# DemoCatV2.net
KiCad netlist of a schematic drawn in Altium Designer
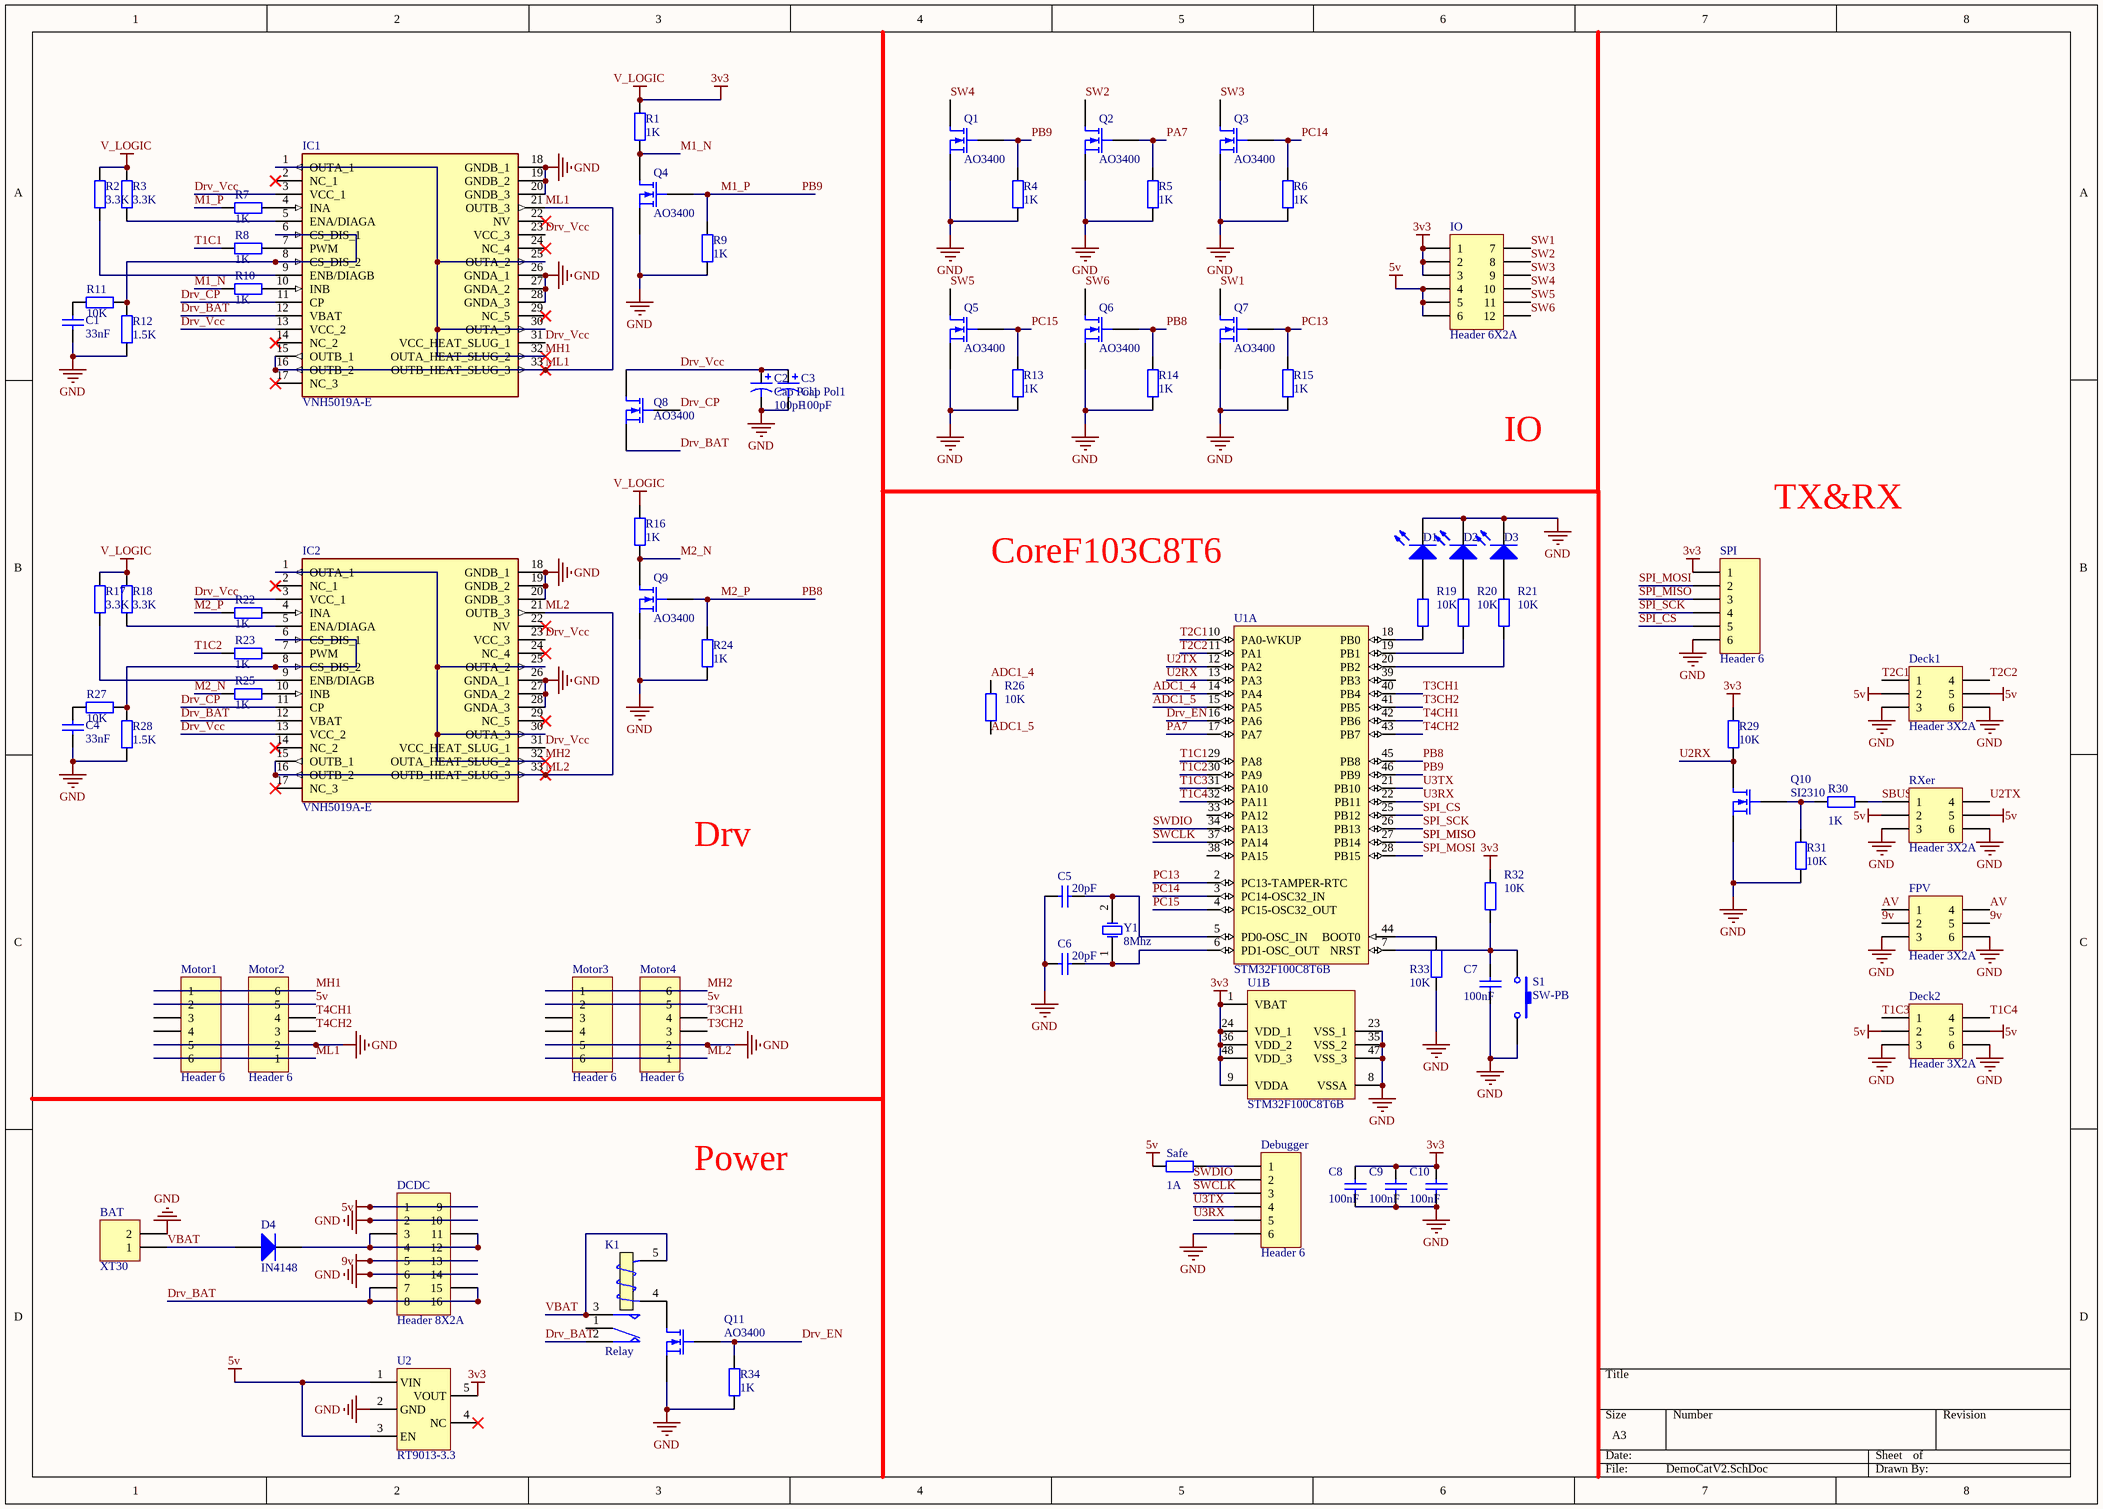
[diagram p0: DemoCatV2.SchDoc]

(export (version "E")
  (design (tool "Eeschema 10.0.6"))
  (components
    (comp (ref "BAT")
      (value "XT30")
      (footprint "XT30-IN-W")
      (description "Header, 2-Pin")
      (fields (field (name "PUBLISHER") "Altium Limited"))
      (libsource (lib "Miscellaneous Connectors") (part "Header 2"))
    )
    (comp (ref "C1")
      (value "33nF")
      (footprint "0603C")
      (description "Capacitor")
      (fields (field (name "Comment") "Cap") (field (name "PUBLISHER") "Altium Limited"))
      (libsource (lib "Miscellaneous Devices") (part "Cap"))
    )
    (comp (ref "C2")
      (value "Cap Pol1")
      (footprint "6.3*7.7-c")
      (description "Polarized Capacitor (Radial)")
      (fields (field (name "ALTIUM_VALUE") "100pF") (field (name "PUBLISHER") "Altium Limited"))
      (libsource (lib "Miscellaneous Devices") (part "Cap Pol1"))
    )
    (comp (ref "C3")
      (value "Cap Pol1")
      (footprint "6.3*7.7-c")
      (description "Polarized Capacitor (Radial)")
      (fields (field (name "ALTIUM_VALUE") "100pF") (field (name "PUBLISHER") "Altium Limited"))
      (libsource (lib "Miscellaneous Devices") (part "Cap Pol1"))
    )
    (comp (ref "C4")
      (value "33nF")
      (footprint "0603C")
      (description "Capacitor")
      (fields (field (name "Comment") "Cap") (field (name "PUBLISHER") "Altium Limited"))
      (libsource (lib "Miscellaneous Devices") (part "Cap"))
    )
    (comp (ref "C5")
      (value "20pF")
      (footprint "0603C")
      (description "Capacitor")
      (fields (field (name "Comment") "Cap") (field (name "PUBLISHER") "Altium Limited"))
      (libsource (lib "Miscellaneous Devices") (part "Cap"))
    )
    (comp (ref "C6")
      (value "20pF")
      (footprint "0603C")
      (description "Capacitor")
      (fields (field (name "Comment") "Cap") (field (name "PUBLISHER") "Altium Limited"))
      (libsource (lib "Miscellaneous Devices") (part "Cap"))
    )
    (comp (ref "C7")
      (value "100nF")
      (footprint "0603C")
      (description "Capacitor")
      (fields (field (name "Comment") "Cap") (field (name "PUBLISHER") "Altium Limited"))
      (libsource (lib "Miscellaneous Devices") (part "Cap"))
    )
    (comp (ref "C8")
      (value "100nF")
      (footprint "0603C")
      (description "Capacitor")
      (fields (field (name "Comment") "Cap") (field (name "PUBLISHER") "Altium Limited"))
      (libsource (lib "Miscellaneous Devices") (part "Cap"))
    )
    (comp (ref "C9")
      (value "100nF")
      (footprint "0603C")
      (description "Capacitor")
      (fields (field (name "Comment") "Cap") (field (name "PUBLISHER") "Altium Limited"))
      (libsource (lib "Miscellaneous Devices") (part "Cap"))
    )
    (comp (ref "C10")
      (value "100nF")
      (footprint "0603C")
      (description "Capacitor")
      (fields (field (name "Comment") "Cap") (field (name "PUBLISHER") "Altium Limited"))
      (libsource (lib "Miscellaneous Devices") (part "Cap"))
    )
    (comp (ref "D1")
      (value "LED0")
      (footprint "0603LED - Red")
      (description "Typical INFRARED GaAs LED")
      (fields (field (name "PUBLISHER") "Altium Limited"))
      (libsource (lib "Miscellaneous Devices") (part "LED0"))
    )
    (comp (ref "D2")
      (value "LED0")
      (footprint "0603LED - Green")
      (description "Typical INFRARED GaAs LED")
      (fields (field (name "PUBLISHER") "Altium Limited"))
      (libsource (lib "Miscellaneous Devices") (part "LED0"))
    )
    (comp (ref "D3")
      (value "LED0")
      (footprint "0603LED - Blue")
      (description "Typical INFRARED GaAs LED")
      (fields (field (name "PUBLISHER") "Altium Limited"))
      (libsource (lib "Miscellaneous Devices") (part "LED0"))
    )
    (comp (ref "D4")
      (value "IN4148")
      (footprint "DO-214AA(SMB)")
      (description "Default Diode")
      (fields (field (name "PUBLISHER") "Altium Limited"))
      (libsource (lib "Miscellaneous Devices") (part "Diode"))
    )
    (comp (ref "DCDC")
      (value "Header 8X2A")
      (footprint "HDR_EDGE_2x8")
      (description "Header, 8-Pin, Dual row")
      (fields (field (name "PUBLISHER") "Altium Limited"))
      (libsource (lib "Miscellaneous Connectors") (part "Header 8X2A"))
    )
    (comp (ref "Debugger")
      (value "Header 6")
      (footprint "GX1.25_T_6P")
      (description "Header, 6-Pin")
      (fields (field (name "PUBLISHER") "Altium Limited"))
      (libsource (lib "") (part "Header 6_1"))
    )
    (comp (ref "Deck1")
      (value "Header 3X2A")
      (footprint "HDR_EDGE_2x3")
      (description "Header, 3-Pin, Dual row")
      (fields (field (name "PUBLISHER") "Altium Limited"))
      (libsource (lib "Miscellaneous Connectors") (part "Header 3X2A"))
    )
    (comp (ref "Deck2")
      (value "Header 3X2A")
      (footprint "HDR_EDGE_2x3")
      (description "Header, 3-Pin, Dual row")
      (fields (field (name "PUBLISHER") "Altium Limited"))
      (libsource (lib "Miscellaneous Connectors") (part "Header 3X2A"))
    )
    (comp (ref "FPV")
      (value "Header 3X2A")
      (footprint "HDR_EDGE_2x3")
      (description "Header, 3-Pin, Dual row")
      (fields (field (name "PUBLISHER") "Altium Limited"))
      (libsource (lib "Miscellaneous Connectors") (part "Header 3X2A"))
    )
    (comp (ref "IC1")
      (value "VNH5019A-E")
      (footprint "VNH5019A-E_1")
      (description "Integrated Circuit")
      (fields (field (name "MOUSER PART NUMBER") "511-VNH5019A-E") (field (name "RS PART NUMBER") "8805550P"))
      (libsource (lib "*") (part "VNH5019A-E"))
    )
    (comp (ref "IC2")
      (value "VNH5019A-E")
      (footprint "VNH5019A-E_1")
      (description "Integrated Circuit")
      (fields (field (name "MOUSER PART NUMBER") "511-VNH5019A-E") (field (name "RS PART NUMBER") "8805550P"))
      (libsource (lib "*") (part "VNH5019A-E"))
    )
    (comp (ref "IO")
      (value "Header 6X2A")
      (footprint "HDR_EDGE_2x6")
      (description "Header, 6-Pin, Dual row")
      (fields (field (name "PUBLISHER") "Altium Limited"))
      (libsource (lib "Miscellaneous Connectors") (part "Header 6X2A"))
    )
    (comp (ref "K1")
      (value "Relay")
      (footprint "RY-HF46-HS1")
      (description "SPDT Relay")
      (fields (field (name "PUBLISHER") "Altium Limited"))
      (libsource (lib "Relay") (part "Relay"))
    )
    (comp (ref "Motor1")
      (value "Header 6")
      (footprint "PH-PS-2.0-6")
      (description "Header, 6-Pin")
      (fields (field (name "PUBLISHER") "Altium Limited"))
      (libsource (lib "") (part "Header 6_1"))
    )
    (comp (ref "Motor2")
      (value "Header 6")
      (footprint "PH-PS-2.0-6")
      (description "Header, 6-Pin")
      (fields (field (name "PUBLISHER") "Altium Limited"))
      (libsource (lib "Miscellaneous Connectors") (part "Header 6"))
    )
    (comp (ref "Motor3")
      (value "Header 6")
      (footprint "PH-PS-2.0-6")
      (description "Header, 6-Pin")
      (fields (field (name "PUBLISHER") "Altium Limited"))
      (libsource (lib "") (part "Header 6_1"))
    )
    (comp (ref "Motor4")
      (value "Header 6")
      (footprint "PH-PS-2.0-6")
      (description "Header, 6-Pin")
      (fields (field (name "PUBLISHER") "Altium Limited"))
      (libsource (lib "Miscellaneous Connectors") (part "Header 6"))
    )
    (comp (ref "Q1")
      (value "AO3400")
      (footprint "SOT-23-MOS")
      (description "N-Channel MOSFET")
      (fields (field (name "PUBLISHER") "Altium Limited"))
      (libsource (lib "Miscellaneous Devices") (part "MOSFET-N"))
    )
    (comp (ref "Q2")
      (value "AO3400")
      (footprint "SOT-23-MOS")
      (description "N-Channel MOSFET")
      (fields (field (name "PUBLISHER") "Altium Limited"))
      (libsource (lib "Miscellaneous Devices") (part "MOSFET-N"))
    )
    (comp (ref "Q3")
      (value "AO3400")
      (footprint "SOT-23-MOS")
      (description "N-Channel MOSFET")
      (fields (field (name "PUBLISHER") "Altium Limited"))
      (libsource (lib "Miscellaneous Devices") (part "MOSFET-N"))
    )
    (comp (ref "Q4")
      (value "AO3400")
      (footprint "SOT-23-MOS")
      (description "N-Channel MOSFET")
      (fields (field (name "PUBLISHER") "Altium Limited"))
      (libsource (lib "Miscellaneous Devices") (part "MOSFET-N"))
    )
    (comp (ref "Q5")
      (value "AO3400")
      (footprint "SOT-23-MOS")
      (description "N-Channel MOSFET")
      (fields (field (name "PUBLISHER") "Altium Limited"))
      (libsource (lib "Miscellaneous Devices") (part "MOSFET-N"))
    )
    (comp (ref "Q6")
      (value "AO3400")
      (footprint "SOT-23-MOS")
      (description "N-Channel MOSFET")
      (fields (field (name "PUBLISHER") "Altium Limited"))
      (libsource (lib "Miscellaneous Devices") (part "MOSFET-N"))
    )
    (comp (ref "Q7")
      (value "AO3400")
      (footprint "SOT-23-MOS")
      (description "N-Channel MOSFET")
      (fields (field (name "PUBLISHER") "Altium Limited"))
      (libsource (lib "Miscellaneous Devices") (part "MOSFET-N"))
    )
    (comp (ref "Q8")
      (value "AO3400")
      (footprint "TO-252-3")
      (description "N-Channel MOSFET")
      (fields (field (name "PUBLISHER") "Altium Limited"))
      (libsource (lib "Miscellaneous Devices") (part "MOSFET-N"))
    )
    (comp (ref "Q9")
      (value "AO3400")
      (footprint "SOT-23-MOS")
      (description "N-Channel MOSFET")
      (fields (field (name "PUBLISHER") "Altium Limited"))
      (libsource (lib "Miscellaneous Devices") (part "MOSFET-N"))
    )
    (comp (ref "Q10")
      (value "SI2310")
      (footprint "SOT-23-MOS")
      (description "N-Channel MOSFET")
      (fields (field (name "PUBLISHER") "Altium Limited"))
      (libsource (lib "Miscellaneous Devices") (part "MOSFET-N"))
    )
    (comp (ref "Q11")
      (value "AO3400")
      (footprint "SOT-23-MOS")
      (description "N-Channel MOSFET")
      (fields (field (name "PUBLISHER") "Altium Limited"))
      (libsource (lib "Miscellaneous Devices") (part "MOSFET-N"))
    )
    (comp (ref "R1")
      (value "1K")
      (footprint "0603R")
      (description "Resistor")
      (fields (field (name "Comment") "Res2") (field (name "PUBLISHER") "Altium Limited"))
      (libsource (lib "") (part "Res2_1"))
    )
    (comp (ref "R2")
      (value "3.3K")
      (footprint "0603R")
      (description "Resistor")
      (fields (field (name "Comment") "Res2") (field (name "PUBLISHER") "Altium Limited"))
      (libsource (lib "") (part "Res2_1"))
    )
    (comp (ref "R3")
      (value "3.3K")
      (footprint "0603R")
      (description "Resistor")
      (fields (field (name "Comment") "Res2") (field (name "PUBLISHER") "Altium Limited"))
      (libsource (lib "") (part "Res2_1"))
    )
    (comp (ref "R4")
      (value "1K")
      (footprint "0603R")
      (description "Resistor")
      (fields (field (name "Comment") "Res2") (field (name "PUBLISHER") "Altium Limited"))
      (libsource (lib "") (part "Res2_1"))
    )
    (comp (ref "R5")
      (value "1K")
      (footprint "0603R")
      (description "Resistor")
      (fields (field (name "Comment") "Res2") (field (name "PUBLISHER") "Altium Limited"))
      (libsource (lib "") (part "Res2_1"))
    )
    (comp (ref "R6")
      (value "1K")
      (footprint "0603R")
      (description "Resistor")
      (fields (field (name "Comment") "Res2") (field (name "PUBLISHER") "Altium Limited"))
      (libsource (lib "") (part "Res2_1"))
    )
    (comp (ref "R7")
      (value "1K")
      (footprint "0603R")
      (description "Resistor")
      (fields (field (name "Comment") "Res2") (field (name "PUBLISHER") "Altium Limited"))
      (libsource (lib "Miscellaneous Devices") (part "Res2"))
    )
    (comp (ref "R8")
      (value "1K")
      (footprint "0603R")
      (description "Resistor")
      (fields (field (name "Comment") "Res2") (field (name "PUBLISHER") "Altium Limited"))
      (libsource (lib "Miscellaneous Devices") (part "Res2"))
    )
    (comp (ref "R9")
      (value "1K")
      (footprint "0603R")
      (description "Resistor")
      (fields (field (name "Comment") "Res2") (field (name "PUBLISHER") "Altium Limited"))
      (libsource (lib "") (part "Res2_1"))
    )
    (comp (ref "R10")
      (value "1K")
      (footprint "0603R")
      (description "Resistor")
      (fields (field (name "Comment") "Res2") (field (name "PUBLISHER") "Altium Limited"))
      (libsource (lib "Miscellaneous Devices") (part "Res2"))
    )
    (comp (ref "R11")
      (value "10K")
      (footprint "0603R")
      (description "Resistor")
      (fields (field (name "Comment") "Res2") (field (name "PUBLISHER") "Altium Limited"))
      (libsource (lib "Miscellaneous Devices") (part "Res2"))
    )
    (comp (ref "R12")
      (value "1.5K")
      (footprint "0603R")
      (description "Resistor")
      (fields (field (name "Comment") "Res2") (field (name "PUBLISHER") "Altium Limited"))
      (libsource (lib "") (part "Res2_1"))
    )
    (comp (ref "R13")
      (value "1K")
      (footprint "0603R")
      (description "Resistor")
      (fields (field (name "Comment") "Res2") (field (name "PUBLISHER") "Altium Limited"))
      (libsource (lib "") (part "Res2_1"))
    )
    (comp (ref "R14")
      (value "1K")
      (footprint "0603R")
      (description "Resistor")
      (fields (field (name "Comment") "Res2") (field (name "PUBLISHER") "Altium Limited"))
      (libsource (lib "") (part "Res2_1"))
    )
    (comp (ref "R15")
      (value "1K")
      (footprint "0603R")
      (description "Resistor")
      (fields (field (name "Comment") "Res2") (field (name "PUBLISHER") "Altium Limited"))
      (libsource (lib "") (part "Res2_1"))
    )
    (comp (ref "R16")
      (value "1K")
      (footprint "0603R")
      (description "Resistor")
      (fields (field (name "Comment") "Res2") (field (name "PUBLISHER") "Altium Limited"))
      (libsource (lib "") (part "Res2_1"))
    )
    (comp (ref "R17")
      (value "3.3K")
      (footprint "0603R")
      (description "Resistor")
      (fields (field (name "Comment") "Res2") (field (name "PUBLISHER") "Altium Limited"))
      (libsource (lib "") (part "Res2_1"))
    )
    (comp (ref "R18")
      (value "3.3K")
      (footprint "0603R")
      (description "Resistor")
      (fields (field (name "Comment") "Res2") (field (name "PUBLISHER") "Altium Limited"))
      (libsource (lib "") (part "Res2_1"))
    )
    (comp (ref "R19")
      (value "10K")
      (footprint "0603R")
      (description "Resistor")
      (fields (field (name "PUBLISHER") "Altium Limited"))
      (libsource (lib "") (part "Res2_1"))
    )
    (comp (ref "R20")
      (value "10K")
      (footprint "0603R")
      (description "Resistor")
      (fields (field (name "PUBLISHER") "Altium Limited"))
      (libsource (lib "") (part "Res2_1"))
    )
    (comp (ref "R21")
      (value "10K")
      (footprint "0603R")
      (description "Resistor")
      (fields (field (name "PUBLISHER") "Altium Limited"))
      (libsource (lib "") (part "Res2_1"))
    )
    (comp (ref "R22")
      (value "1K")
      (footprint "0603R")
      (description "Resistor")
      (fields (field (name "Comment") "Res2") (field (name "PUBLISHER") "Altium Limited"))
      (libsource (lib "Miscellaneous Devices") (part "Res2"))
    )
    (comp (ref "R23")
      (value "1K")
      (footprint "0603R")
      (description "Resistor")
      (fields (field (name "Comment") "Res2") (field (name "PUBLISHER") "Altium Limited"))
      (libsource (lib "Miscellaneous Devices") (part "Res2"))
    )
    (comp (ref "R24")
      (value "1K")
      (footprint "0603R")
      (description "Resistor")
      (fields (field (name "Comment") "Res2") (field (name "PUBLISHER") "Altium Limited"))
      (libsource (lib "") (part "Res2_1"))
    )
    (comp (ref "R25")
      (value "1K")
      (footprint "0603R")
      (description "Resistor")
      (fields (field (name "Comment") "Res2") (field (name "PUBLISHER") "Altium Limited"))
      (libsource (lib "Miscellaneous Devices") (part "Res2"))
    )
    (comp (ref "R26")
      (value "10K")
      (footprint "1206R")
      (description "Resistor")
      (fields (field (name "PUBLISHER") "Altium Limited"))
      (libsource (lib "") (part "Res2_1"))
    )
    (comp (ref "R27")
      (value "10K")
      (footprint "0603R")
      (description "Resistor")
      (fields (field (name "Comment") "Res2") (field (name "PUBLISHER") "Altium Limited"))
      (libsource (lib "Miscellaneous Devices") (part "Res2"))
    )
    (comp (ref "R28")
      (value "1.5K")
      (footprint "0603R")
      (description "Resistor")
      (fields (field (name "Comment") "Res2") (field (name "PUBLISHER") "Altium Limited"))
      (libsource (lib "") (part "Res2_1"))
    )
    (comp (ref "R29")
      (value "10K")
      (footprint "0603R")
      (description "Resistor")
      (fields (field (name "Comment") "Res2") (field (name "PUBLISHER") "Altium Limited"))
      (libsource (lib "") (part "Res2_1"))
    )
    (comp (ref "R30")
      (value "1K")
      (footprint "0603R")
      (description "Resistor")
      (fields (field (name "Comment") "Res2") (field (name "PUBLISHER") "Altium Limited"))
      (libsource (lib "") (part "Res2_2"))
    )
    (comp (ref "R31")
      (value "10K")
      (footprint "0603R")
      (description "Resistor")
      (fields (field (name "Comment") "Res2") (field (name "PUBLISHER") "Altium Limited"))
      (libsource (lib "") (part "Res2_1"))
    )
    (comp (ref "R32")
      (value "10K")
      (footprint "0603R")
      (description "Resistor")
      (fields (field (name "PUBLISHER") "Altium Limited"))
      (libsource (lib "") (part "Res2_1"))
    )
    (comp (ref "R33")
      (value "10K")
      (footprint "0603R")
      (description "Resistor")
      (fields (field (name "Comment") "Res2") (field (name "PUBLISHER") "Altium Limited"))
      (libsource (lib "") (part "Res2_1"))
    )
    (comp (ref "R34")
      (value "1K")
      (footprint "0603R")
      (description "Resistor")
      (fields (field (name "Comment") "Res2") (field (name "PUBLISHER") "Altium Limited"))
      (libsource (lib "") (part "Res2_1"))
    )
    (comp (ref "RXer")
      (value "Header 3X2A")
      (footprint "HDR_EDGE_2x3")
      (description "Header, 3-Pin, Dual row")
      (fields (field (name "PUBLISHER") "Altium Limited"))
      (libsource (lib "Miscellaneous Connectors") (part "Header 3X2A"))
    )
    (comp (ref "S1")
      (value "SW-PB")
      (footprint "KeySwitch-3X3")
      (description "Switch")
      (fields (field (name "PUBLISHER") "Altium Limited"))
      (libsource (lib "Miscellaneous Devices") (part "SW-PB"))
    )
    (comp (ref "Safe")
      (value "1A")
      (footprint "Maxwell_LIB:0805R")
      (description "Resistor")
      (fields (field (name "Comment") "Res2") (field (name "PUBLISHER") "Altium Limited"))
      (libsource (lib "") (part "Res2_2"))
    )
    (comp (ref "SPI")
      (value "Header 6")
      (footprint "GX1.25_T_6P")
      (description "Header, 6-Pin")
      (fields (field (name "PUBLISHER") "Altium Limited"))
      (libsource (lib "") (part "Header 6_1"))
    )
    (comp (ref "U1")
      (value "STM32F100C8T6B")
      (footprint "STM-LQFP48_N")
      (libsource (lib "STM32F1") (part "STM32F100C8T6B"))
    )
    (comp (ref "U2")
      (value "RT9013-3.3")
      (footprint "SOT-23-5")
      (description "3.3V 500mA")
      (libsource (lib "My_Library") (part "RT9013"))
    )
    (comp (ref "Y1")
      (value "8Mhz")
      (footprint "OSC 3215-2P")
      (fields (field (name "PUBLISHER") "Altium Limited"))
      (libsource (lib "Miscellaneous Devices") (part "XTAL"))
    )
  )
  (nets
    (net (code "1") (name "/ADC1_4") (class "Default")
      (node (ref "R26") (pin "2") (pinfunction "2_2") (pintype "passive"))
      (node (ref "U1") (pin "14") (pinfunction "PA4_14") (pintype "bidirectional"))
    )
    (net (code "2") (name "/ADC1_5") (class "Default")
      (node (ref "R26") (pin "1") (pinfunction "1_1") (pintype "passive"))
      (node (ref "U1") (pin "15") (pinfunction "PA5_15") (pintype "bidirectional"))
    )
    (net (code "3") (name "/AV") (class "Default")
      (node (ref "FPV") (pin "1") (pinfunction "1_1") (pintype "passive"))
      (node (ref "FPV") (pin "4") (pinfunction "4_4") (pintype "passive"))
    )
    (net (code "4") (name "/Drv_BAT") (class "Default")
      (node (ref "DCDC") (pin "15") (pinfunction "15_15") (pintype "passive"))
      (node (ref "DCDC") (pin "16") (pinfunction "16_16") (pintype "passive"))
      (node (ref "DCDC") (pin "7") (pinfunction "7_7") (pintype "passive"))
      (node (ref "DCDC") (pin "8") (pinfunction "8_8") (pintype "passive"))
      (node (ref "IC1") (pin "12") (pinfunction "VBAT_12") (pintype "passive"))
      (node (ref "IC2") (pin "12") (pinfunction "VBAT_12") (pintype "passive"))
      (node (ref "K1") (pin "2") (pinfunction "NC_2") (pintype "passive"))
      (node (ref "Q8") (pin "3") (pinfunction "S_3") (pintype "passive"))
    )
    (net (code "5") (name "/Drv_CP") (class "Default")
      (node (ref "IC1") (pin "11") (pinfunction "CP_11") (pintype "passive"))
      (node (ref "IC2") (pin "11") (pinfunction "CP_11") (pintype "passive"))
      (node (ref "Q8") (pin "2") (pinfunction "G_2") (pintype "passive"))
    )
    (net (code "6") (name "/Drv_EN") (class "Default")
      (node (ref "Q11") (pin "2") (pinfunction "G_2") (pintype "passive"))
      (node (ref "R34") (pin "2") (pinfunction "2_2") (pintype "passive"))
      (node (ref "U1") (pin "16") (pinfunction "PA6_16") (pintype "bidirectional"))
    )
    (net (code "7") (name "/Drv_Vcc") (class "Default")
      (node (ref "C2") (pin "1") (pinfunction "1_1") (pintype "passive"))
      (node (ref "C3") (pin "1") (pinfunction "1_1") (pintype "passive"))
      (node (ref "IC1") (pin "13") (pinfunction "VCC_2_13") (pintype "power_in"))
      (node (ref "IC1") (pin "23") (pinfunction "VCC_3_23") (pintype "power_in"))
      (node (ref "IC1") (pin "3") (pinfunction "VCC_1_3") (pintype "power_in"))
      (node (ref "IC1") (pin "31") (pinfunction "VCC_HEAT_SLUG_1_31") (pintype "power_in"))
      (node (ref "IC2") (pin "13") (pinfunction "VCC_2_13") (pintype "power_in"))
      (node (ref "IC2") (pin "23") (pinfunction "VCC_3_23") (pintype "power_in"))
      (node (ref "IC2") (pin "3") (pinfunction "VCC_1_3") (pintype "power_in"))
      (node (ref "IC2") (pin "31") (pinfunction "VCC_HEAT_SLUG_1_31") (pintype "power_in"))
      (node (ref "Q8") (pin "1") (pinfunction "D_1") (pintype "passive"))
    )
    (net (code "8") (name "/M1_N") (class "Default")
      (node (ref "Q4") (pin "1") (pinfunction "D_1") (pintype "passive"))
      (node (ref "R1") (pin "1") (pinfunction "1_1") (pintype "passive"))
      (node (ref "R10") (pin "2") (pinfunction "2_2") (pintype "passive"))
    )
    (net (code "9") (name "/M1_P") (class "Default")
      (node (ref "Q1") (pin "2") (pinfunction "G_2") (pintype "passive"))
      (node (ref "Q4") (pin "2") (pinfunction "G_2") (pintype "passive"))
      (node (ref "R4") (pin "2") (pinfunction "2_2") (pintype "passive"))
      (node (ref "R7") (pin "2") (pinfunction "2_2") (pintype "passive"))
      (node (ref "R9") (pin "2") (pinfunction "2_2") (pintype "passive"))
      (node (ref "U1") (pin "46") (pinfunction "PB9_46") (pintype "bidirectional"))
    )
    (net (code "10") (name "/M2_N") (class "Default")
      (node (ref "Q9") (pin "1") (pinfunction "D_1") (pintype "passive"))
      (node (ref "R16") (pin "1") (pinfunction "1_1") (pintype "passive"))
      (node (ref "R25") (pin "2") (pinfunction "2_2") (pintype "passive"))
    )
    (net (code "11") (name "/M2_P") (class "Default")
      (node (ref "Q6") (pin "2") (pinfunction "G_2") (pintype "passive"))
      (node (ref "Q9") (pin "2") (pinfunction "G_2") (pintype "passive"))
      (node (ref "R14") (pin "2") (pinfunction "2_2") (pintype "passive"))
      (node (ref "R22") (pin "2") (pinfunction "2_2") (pintype "passive"))
      (node (ref "R24") (pin "2") (pinfunction "2_2") (pintype "passive"))
      (node (ref "U1") (pin "45") (pinfunction "PB8_45") (pintype "bidirectional"))
    )
    (net (code "12") (name "/MH1") (class "Default")
      (node (ref "IC1") (pin "1") (pinfunction "OUTA_1_1") (pintype "output"))
      (node (ref "IC1") (pin "25") (pinfunction "OUTA_2_25") (pintype "output"))
      (node (ref "IC1") (pin "30") (pinfunction "OUTA_3_30") (pintype "output"))
      (node (ref "IC1") (pin "32") (pinfunction "OUTA_HEAT_SLUG_2_32") (pintype "output"))
      (node (ref "Motor1") (pin "1") (pinfunction "1_1") (pintype "passive"))
      (node (ref "Motor2") (pin "6") (pinfunction "6_6") (pintype "passive"))
    )
    (net (code "13") (name "/MH2") (class "Default")
      (node (ref "IC2") (pin "1") (pinfunction "OUTA_1_1") (pintype "output"))
      (node (ref "IC2") (pin "25") (pinfunction "OUTA_2_25") (pintype "output"))
      (node (ref "IC2") (pin "30") (pinfunction "OUTA_3_30") (pintype "output"))
      (node (ref "IC2") (pin "32") (pinfunction "OUTA_HEAT_SLUG_2_32") (pintype "output"))
      (node (ref "Motor3") (pin "1") (pinfunction "1_1") (pintype "passive"))
      (node (ref "Motor4") (pin "6") (pinfunction "6_6") (pintype "passive"))
    )
    (net (code "14") (name "/ML1") (class "Default")
      (node (ref "IC1") (pin "15") (pinfunction "OUTB_1_15") (pintype "output"))
      (node (ref "IC1") (pin "16") (pinfunction "OUTB_2_16") (pintype "output"))
      (node (ref "IC1") (pin "21") (pinfunction "OUTB_3_21") (pintype "output"))
      (node (ref "IC1") (pin "33") (pinfunction "OUTB_HEAT_SLUG_3_33") (pintype "output"))
      (node (ref "Motor1") (pin "6") (pinfunction "6_6") (pintype "passive"))
      (node (ref "Motor2") (pin "1") (pinfunction "1_1") (pintype "passive"))
    )
    (net (code "15") (name "/ML2") (class "Default")
      (node (ref "IC2") (pin "15") (pinfunction "OUTB_1_15") (pintype "output"))
      (node (ref "IC2") (pin "16") (pinfunction "OUTB_2_16") (pintype "output"))
      (node (ref "IC2") (pin "21") (pinfunction "OUTB_3_21") (pintype "output"))
      (node (ref "IC2") (pin "33") (pinfunction "OUTB_HEAT_SLUG_3_33") (pintype "output"))
      (node (ref "Motor3") (pin "6") (pinfunction "6_6") (pintype "passive"))
      (node (ref "Motor4") (pin "1") (pinfunction "1_1") (pintype "passive"))
    )
    (net (code "16") (name "/PA7") (class "Default")
      (node (ref "Q2") (pin "2") (pinfunction "G_2") (pintype "passive"))
      (node (ref "R5") (pin "2") (pinfunction "2_2") (pintype "passive"))
      (node (ref "U1") (pin "17") (pinfunction "PA7_17") (pintype "bidirectional"))
    )
    (net (code "17") (name "/PC13") (class "Default")
      (node (ref "Q7") (pin "2") (pinfunction "G_2") (pintype "passive"))
      (node (ref "R15") (pin "2") (pinfunction "2_2") (pintype "passive"))
      (node (ref "U1") (pin "2") (pinfunction "PC13-TAMPER-RTC_2") (pintype "bidirectional"))
    )
    (net (code "18") (name "/PC14") (class "Default")
      (node (ref "Q3") (pin "2") (pinfunction "G_2") (pintype "passive"))
      (node (ref "R6") (pin "2") (pinfunction "2_2") (pintype "passive"))
      (node (ref "U1") (pin "3") (pinfunction "PC14-OSC32_IN_3") (pintype "bidirectional"))
    )
    (net (code "19") (name "/PC15") (class "Default")
      (node (ref "Q5") (pin "2") (pinfunction "G_2") (pintype "passive"))
      (node (ref "R13") (pin "2") (pinfunction "2_2") (pintype "passive"))
      (node (ref "U1") (pin "4") (pinfunction "PC15-OSC32_OUT_4") (pintype "bidirectional"))
    )
    (net (code "20") (name "/SBUS") (class "Default")
      (node (ref "R30") (pin "2") (pinfunction "2_2") (pintype "passive"))
      (node (ref "RXer") (pin "1") (pinfunction "1_1") (pintype "passive"))
    )
    (net (code "21") (name "/SPI_CS") (class "Default")
      (node (ref "SPI") (pin "5") (pinfunction "5_5") (pintype "passive"))
      (node (ref "U1") (pin "25") (pinfunction "PB12_25") (pintype "bidirectional"))
    )
    (net (code "22") (name "/SPI_MISO") (class "Default")
      (node (ref "SPI") (pin "3") (pinfunction "3_3") (pintype "passive"))
      (node (ref "U1") (pin "27") (pinfunction "PB14_27") (pintype "bidirectional"))
    )
    (net (code "23") (name "/SPI_MOSI") (class "Default")
      (node (ref "SPI") (pin "2") (pinfunction "2_2") (pintype "passive"))
      (node (ref "U1") (pin "28") (pinfunction "PB15_28") (pintype "bidirectional"))
    )
    (net (code "24") (name "/SPI_SCK") (class "Default")
      (node (ref "SPI") (pin "4") (pinfunction "4_4") (pintype "passive"))
      (node (ref "U1") (pin "26") (pinfunction "PB13_26") (pintype "bidirectional"))
    )
    (net (code "25") (name "/SW1") (class "Default")
      (node (ref "IO") (pin "7") (pinfunction "7_7") (pintype "passive"))
      (node (ref "Q7") (pin "1") (pinfunction "D_1") (pintype "passive"))
    )
    (net (code "26") (name "/SW2") (class "Default")
      (node (ref "IO") (pin "8") (pinfunction "8_8") (pintype "passive"))
      (node (ref "Q2") (pin "1") (pinfunction "D_1") (pintype "passive"))
    )
    (net (code "27") (name "/SW3") (class "Default")
      (node (ref "IO") (pin "9") (pinfunction "9_9") (pintype "passive"))
      (node (ref "Q3") (pin "1") (pinfunction "D_1") (pintype "passive"))
    )
    (net (code "28") (name "/SW4") (class "Default")
      (node (ref "IO") (pin "10") (pinfunction "10_10") (pintype "passive"))
      (node (ref "Q1") (pin "1") (pinfunction "D_1") (pintype "passive"))
    )
    (net (code "29") (name "/SW5") (class "Default")
      (node (ref "IO") (pin "11") (pinfunction "11_11") (pintype "passive"))
      (node (ref "Q5") (pin "1") (pinfunction "D_1") (pintype "passive"))
    )
    (net (code "30") (name "/SW6") (class "Default")
      (node (ref "IO") (pin "12") (pinfunction "12_12") (pintype "passive"))
      (node (ref "Q6") (pin "1") (pinfunction "D_1") (pintype "passive"))
    )
    (net (code "31") (name "/SWCLK") (class "Default")
      (node (ref "Debugger") (pin "3") (pinfunction "3_3") (pintype "passive"))
      (node (ref "U1") (pin "37") (pinfunction "PA14_37") (pintype "bidirectional"))
    )
    (net (code "32") (name "/SWDIO") (class "Default")
      (node (ref "Debugger") (pin "2") (pinfunction "2_2") (pintype "passive"))
      (node (ref "U1") (pin "34") (pinfunction "PA13_34") (pintype "bidirectional"))
    )
    (net (code "33") (name "/T1C1") (class "Default")
      (node (ref "R8") (pin "2") (pinfunction "2_2") (pintype "passive"))
      (node (ref "U1") (pin "29") (pinfunction "PA8_29") (pintype "bidirectional"))
    )
    (net (code "34") (name "/T1C2") (class "Default")
      (node (ref "R23") (pin "2") (pinfunction "2_2") (pintype "passive"))
      (node (ref "U1") (pin "30") (pinfunction "PA9_30") (pintype "bidirectional"))
    )
    (net (code "35") (name "/T1C3") (class "Default")
      (node (ref "Deck2") (pin "1") (pinfunction "1_1") (pintype "passive"))
      (node (ref "U1") (pin "31") (pinfunction "PA10_31") (pintype "bidirectional"))
    )
    (net (code "36") (name "/T1C4") (class "Default")
      (node (ref "Deck2") (pin "4") (pinfunction "4_4") (pintype "passive"))
      (node (ref "U1") (pin "32") (pinfunction "PA11_32") (pintype "bidirectional"))
    )
    (net (code "37") (name "/T2C1") (class "Default")
      (node (ref "Deck1") (pin "1") (pinfunction "1_1") (pintype "passive"))
      (node (ref "U1") (pin "10") (pinfunction "PA0-WKUP_10") (pintype "bidirectional"))
    )
    (net (code "38") (name "/T2C2") (class "Default")
      (node (ref "Deck1") (pin "4") (pinfunction "4_4") (pintype "passive"))
      (node (ref "U1") (pin "11") (pinfunction "PA1_11") (pintype "bidirectional"))
    )
    (net (code "39") (name "/T3CH1") (class "Default")
      (node (ref "Motor4") (pin "4") (pinfunction "4_4") (pintype "passive"))
      (node (ref "U1") (pin "40") (pinfunction "PB4_40") (pintype "bidirectional"))
    )
    (net (code "40") (name "/T3CH2") (class "Default")
      (node (ref "Motor4") (pin "3") (pinfunction "3_3") (pintype "passive"))
      (node (ref "U1") (pin "41") (pinfunction "PB5_41") (pintype "bidirectional"))
    )
    (net (code "41") (name "/T4CH1") (class "Default")
      (node (ref "Motor2") (pin "4") (pinfunction "4_4") (pintype "passive"))
      (node (ref "U1") (pin "42") (pinfunction "PB6_42") (pintype "bidirectional"))
    )
    (net (code "42") (name "/T4CH2") (class "Default")
      (node (ref "Motor2") (pin "3") (pinfunction "3_3") (pintype "passive"))
      (node (ref "U1") (pin "43") (pinfunction "PB7_43") (pintype "bidirectional"))
    )
    (net (code "43") (name "/U2RX") (class "Default")
      (node (ref "Q10") (pin "1") (pinfunction "D_1") (pintype "passive"))
      (node (ref "R29") (pin "1") (pinfunction "1_1") (pintype "passive"))
      (node (ref "U1") (pin "13") (pinfunction "PA3_13") (pintype "bidirectional"))
    )
    (net (code "44") (name "/U2TX") (class "Default")
      (node (ref "RXer") (pin "4") (pinfunction "4_4") (pintype "passive"))
      (node (ref "U1") (pin "12") (pinfunction "PA2_12") (pintype "bidirectional"))
    )
    (net (code "45") (name "/U3RX") (class "Default")
      (node (ref "Debugger") (pin "5") (pinfunction "5_5") (pintype "passive"))
      (node (ref "U1") (pin "22") (pinfunction "PB11_22") (pintype "bidirectional"))
    )
    (net (code "46") (name "/U3TX") (class "Default")
      (node (ref "Debugger") (pin "4") (pinfunction "4_4") (pintype "passive"))
      (node (ref "U1") (pin "21") (pinfunction "PB10_21") (pintype "bidirectional"))
    )
    (net (code "47") (name "/VBAT") (class "Default")
      (node (ref "BAT") (pin "1") (pinfunction "1_1") (pintype "passive"))
      (node (ref "D4") (pin "1") (pinfunction "A_1") (pintype "passive"))
      (node (ref "K1") (pin "3") (pinfunction "NO_3") (pintype "passive"))
      (node (ref "K1") (pin "5") (pinfunction "T2_5") (pintype "passive"))
    )
    (net (code "48") (name "3v3") (class "Default")
      (node (ref "C10") (pin "2") (pinfunction "2_2") (pintype "passive"))
      (node (ref "C8") (pin "2") (pinfunction "2_2") (pintype "passive"))
      (node (ref "C9") (pin "2") (pinfunction "2_2") (pintype "passive"))
      (node (ref "IO") (pin "1") (pinfunction "1_1") (pintype "passive"))
      (node (ref "IO") (pin "2") (pinfunction "2_2") (pintype "passive"))
      (node (ref "IO") (pin "3") (pinfunction "3_3") (pintype "passive"))
      (node (ref "R1") (pin "2") (pinfunction "2_2") (pintype "passive"))
      (node (ref "R16") (pin "2") (pinfunction "2_2") (pintype "passive"))
      (node (ref "R17") (pin "2") (pinfunction "2_2") (pintype "passive"))
      (node (ref "R18") (pin "2") (pinfunction "2_2") (pintype "passive"))
      (node (ref "R2") (pin "2") (pinfunction "2_2") (pintype "passive"))
      (node (ref "R29") (pin "2") (pinfunction "2_2") (pintype "passive"))
      (node (ref "R3") (pin "2") (pinfunction "2_2") (pintype "passive"))
      (node (ref "R32") (pin "2") (pinfunction "2_2") (pintype "passive"))
      (node (ref "SPI") (pin "1") (pinfunction "1_1") (pintype "passive"))
      (node (ref "U1") (pin "1") (pinfunction "VBAT_1") (pintype "power_in"))
      (node (ref "U1") (pin "24") (pinfunction "VDD_1_24") (pintype "power_in"))
      (node (ref "U1") (pin "36") (pinfunction "VDD_2_36") (pintype "power_in"))
      (node (ref "U1") (pin "48") (pinfunction "VDD_3_48") (pintype "power_in"))
      (node (ref "U1") (pin "9") (pinfunction "VDDA_9") (pintype "power_in"))
      (node (ref "U2") (pin "5") (pinfunction "VOUT_5") (pintype "passive"))
    )
    (net (code "49") (name "5v") (class "Default")
      (node (ref "DCDC") (pin "1") (pinfunction "1_1") (pintype "passive"))
      (node (ref "DCDC") (pin "9") (pinfunction "9_9") (pintype "passive"))
      (node (ref "Deck1") (pin "2") (pinfunction "2_2") (pintype "passive"))
      (node (ref "Deck1") (pin "5") (pinfunction "5_5") (pintype "passive"))
      (node (ref "Deck2") (pin "2") (pinfunction "2_2") (pintype "passive"))
      (node (ref "Deck2") (pin "5") (pinfunction "5_5") (pintype "passive"))
      (node (ref "IO") (pin "4") (pinfunction "4_4") (pintype "passive"))
      (node (ref "IO") (pin "5") (pinfunction "5_5") (pintype "passive"))
      (node (ref "IO") (pin "6") (pinfunction "6_6") (pintype "passive"))
      (node (ref "Motor1") (pin "2") (pinfunction "2_2") (pintype "passive"))
      (node (ref "Motor2") (pin "5") (pinfunction "5_5") (pintype "passive"))
      (node (ref "Motor3") (pin "2") (pinfunction "2_2") (pintype "passive"))
      (node (ref "Motor4") (pin "5") (pinfunction "5_5") (pintype "passive"))
      (node (ref "RXer") (pin "2") (pinfunction "2_2") (pintype "passive"))
      (node (ref "RXer") (pin "5") (pinfunction "5_5") (pintype "passive"))
      (node (ref "Safe") (pin "1") (pinfunction "1_1") (pintype "passive"))
      (node (ref "U2") (pin "1") (pinfunction "VIN_1") (pintype "passive"))
      (node (ref "U2") (pin "3") (pinfunction "EN_3") (pintype "passive"))
    )
    (net (code "50") (name "9v") (class "Default")
      (node (ref "DCDC") (pin "13") (pinfunction "13_13") (pintype "passive"))
      (node (ref "DCDC") (pin "5") (pinfunction "5_5") (pintype "passive"))
      (node (ref "FPV") (pin "2") (pinfunction "2_2") (pintype "passive"))
      (node (ref "FPV") (pin "5") (pinfunction "5_5") (pintype "passive"))
    )
    (net (code "51") (name "GND") (class "Default")
      (node (ref "BAT") (pin "2") (pinfunction "2_2") (pintype "passive"))
      (node (ref "C1") (pin "1") (pinfunction "1_1") (pintype "passive"))
      (node (ref "C10") (pin "1") (pinfunction "1_1") (pintype "passive"))
      (node (ref "C2") (pin "2") (pinfunction "2_2") (pintype "passive"))
      (node (ref "C3") (pin "2") (pinfunction "2_2") (pintype "passive"))
      (node (ref "C4") (pin "1") (pinfunction "1_1") (pintype "passive"))
      (node (ref "C5") (pin "1") (pinfunction "1_1") (pintype "passive"))
      (node (ref "C6") (pin "1") (pinfunction "1_1") (pintype "passive"))
      (node (ref "C7") (pin "1") (pinfunction "1_1") (pintype "passive"))
      (node (ref "C8") (pin "1") (pinfunction "1_1") (pintype "passive"))
      (node (ref "C9") (pin "1") (pinfunction "1_1") (pintype "passive"))
      (node (ref "D1") (pin "2") (pinfunction "K_2") (pintype "passive"))
      (node (ref "D2") (pin "2") (pinfunction "K_2") (pintype "passive"))
      (node (ref "D3") (pin "2") (pinfunction "K_2") (pintype "passive"))
      (node (ref "DCDC") (pin "10") (pinfunction "10_10") (pintype "passive"))
      (node (ref "DCDC") (pin "14") (pinfunction "14_14") (pintype "passive"))
      (node (ref "DCDC") (pin "2") (pinfunction "2_2") (pintype "passive"))
      (node (ref "DCDC") (pin "6") (pinfunction "6_6") (pintype "passive"))
      (node (ref "Debugger") (pin "6") (pinfunction "6_6") (pintype "passive"))
      (node (ref "Deck1") (pin "3") (pinfunction "3_3") (pintype "passive"))
      (node (ref "Deck1") (pin "6") (pinfunction "6_6") (pintype "passive"))
      (node (ref "Deck2") (pin "3") (pinfunction "3_3") (pintype "passive"))
      (node (ref "Deck2") (pin "6") (pinfunction "6_6") (pintype "passive"))
      (node (ref "FPV") (pin "3") (pinfunction "3_3") (pintype "passive"))
      (node (ref "FPV") (pin "6") (pinfunction "6_6") (pintype "passive"))
      (node (ref "IC1") (pin "18") (pinfunction "GNDB_1_18") (pintype "power_in"))
      (node (ref "IC1") (pin "19") (pinfunction "GNDB_2_19") (pintype "power_in"))
      (node (ref "IC1") (pin "20") (pinfunction "GNDB_3_20") (pintype "power_in"))
      (node (ref "IC1") (pin "26") (pinfunction "GNDA_1_26") (pintype "power_in"))
      (node (ref "IC1") (pin "27") (pinfunction "GNDA_2_27") (pintype "power_in"))
      (node (ref "IC1") (pin "28") (pinfunction "GNDA_3_28") (pintype "power_in"))
      (node (ref "IC2") (pin "18") (pinfunction "GNDB_1_18") (pintype "power_in"))
      (node (ref "IC2") (pin "19") (pinfunction "GNDB_2_19") (pintype "power_in"))
      (node (ref "IC2") (pin "20") (pinfunction "GNDB_3_20") (pintype "power_in"))
      (node (ref "IC2") (pin "26") (pinfunction "GNDA_1_26") (pintype "power_in"))
      (node (ref "IC2") (pin "27") (pinfunction "GNDA_2_27") (pintype "power_in"))
      (node (ref "IC2") (pin "28") (pinfunction "GNDA_3_28") (pintype "power_in"))
      (node (ref "Motor1") (pin "5") (pinfunction "5_5") (pintype "passive"))
      (node (ref "Motor2") (pin "2") (pinfunction "2_2") (pintype "passive"))
      (node (ref "Motor3") (pin "5") (pinfunction "5_5") (pintype "passive"))
      (node (ref "Motor4") (pin "2") (pinfunction "2_2") (pintype "passive"))
      (node (ref "Q1") (pin "3") (pinfunction "S_3") (pintype "passive"))
      (node (ref "Q10") (pin "3") (pinfunction "S_3") (pintype "passive"))
      (node (ref "Q11") (pin "3") (pinfunction "S_3") (pintype "passive"))
      (node (ref "Q2") (pin "3") (pinfunction "S_3") (pintype "passive"))
      (node (ref "Q3") (pin "3") (pinfunction "S_3") (pintype "passive"))
      (node (ref "Q4") (pin "3") (pinfunction "S_3") (pintype "passive"))
      (node (ref "Q5") (pin "3") (pinfunction "S_3") (pintype "passive"))
      (node (ref "Q6") (pin "3") (pinfunction "S_3") (pintype "passive"))
      (node (ref "Q7") (pin "3") (pinfunction "S_3") (pintype "passive"))
      (node (ref "Q9") (pin "3") (pinfunction "S_3") (pintype "passive"))
      (node (ref "R12") (pin "1") (pinfunction "1_1") (pintype "passive"))
      (node (ref "R13") (pin "1") (pinfunction "1_1") (pintype "passive"))
      (node (ref "R14") (pin "1") (pinfunction "1_1") (pintype "passive"))
      (node (ref "R15") (pin "1") (pinfunction "1_1") (pintype "passive"))
      (node (ref "R24") (pin "1") (pinfunction "1_1") (pintype "passive"))
      (node (ref "R28") (pin "1") (pinfunction "1_1") (pintype "passive"))
      (node (ref "R31") (pin "1") (pinfunction "1_1") (pintype "passive"))
      (node (ref "R33") (pin "1") (pinfunction "1_1") (pintype "passive"))
      (node (ref "R34") (pin "1") (pinfunction "1_1") (pintype "passive"))
      (node (ref "R4") (pin "1") (pinfunction "1_1") (pintype "passive"))
      (node (ref "R5") (pin "1") (pinfunction "1_1") (pintype "passive"))
      (node (ref "R6") (pin "1") (pinfunction "1_1") (pintype "passive"))
      (node (ref "R9") (pin "1") (pinfunction "1_1") (pintype "passive"))
      (node (ref "RXer") (pin "3") (pinfunction "3_3") (pintype "passive"))
      (node (ref "RXer") (pin "6") (pinfunction "6_6") (pintype "passive"))
      (node (ref "S1") (pin "2") (pinfunction "2_2") (pintype "passive"))
      (node (ref "SPI") (pin "6") (pinfunction "6_6") (pintype "passive"))
      (node (ref "U1") (pin "23") (pinfunction "VSS_1_23") (pintype "power_in"))
      (node (ref "U1") (pin "35") (pinfunction "VSS_2_35") (pintype "power_in"))
      (node (ref "U1") (pin "47") (pinfunction "VSS_3_47") (pintype "power_in"))
      (node (ref "U1") (pin "8") (pinfunction "VSSA_8") (pintype "power_in"))
      (node (ref "U2") (pin "2") (pinfunction "GND_2") (pintype "passive"))
    )
    (net (code "52") (name "Net-(C1-Pad2)") (class "Default")
      (node (ref "C1") (pin "2") (pinfunction "2_2") (pintype "passive"))
      (node (ref "R11") (pin "2") (pinfunction "2_2") (pintype "passive"))
    )
    (net (code "53") (name "Net-(C4-Pad2)") (class "Default")
      (node (ref "C4") (pin "2") (pinfunction "2_2") (pintype "passive"))
      (node (ref "R27") (pin "2") (pinfunction "2_2") (pintype "passive"))
    )
    (net (code "54") (name "Net-(D1-A)") (class "Default")
      (node (ref "D1") (pin "1") (pinfunction "A_1") (pintype "passive"))
      (node (ref "R19") (pin "2") (pinfunction "2_2") (pintype "passive"))
    )
    (net (code "55") (name "Net-(D2-A)") (class "Default")
      (node (ref "D2") (pin "1") (pinfunction "A_1") (pintype "passive"))
      (node (ref "R20") (pin "2") (pinfunction "2_2") (pintype "passive"))
    )
    (net (code "56") (name "Net-(D3-A)") (class "Default")
      (node (ref "D3") (pin "1") (pinfunction "A_1") (pintype "passive"))
      (node (ref "R21") (pin "2") (pinfunction "2_2") (pintype "passive"))
    )
    (net (code "57") (name "Net-(D4-K)") (class "Default")
      (node (ref "D4") (pin "2") (pinfunction "K_2") (pintype "passive"))
      (node (ref "DCDC") (pin "11") (pinfunction "11_11") (pintype "passive"))
      (node (ref "DCDC") (pin "12") (pinfunction "12_12") (pintype "passive"))
      (node (ref "DCDC") (pin "3") (pinfunction "3_3") (pintype "passive"))
      (node (ref "DCDC") (pin "4") (pinfunction "4_4") (pintype "passive"))
    )
    (net (code "58") (name "Net-(Debugger-Pad1)") (class "Default")
      (node (ref "Debugger") (pin "1") (pinfunction "1_1") (pintype "passive"))
      (node (ref "Safe") (pin "2") (pinfunction "2_2") (pintype "passive"))
    )
    (net (code "59") (name "Net-(IC1-CS_DIS_1)") (class "Default")
      (node (ref "IC1") (pin "6") (pinfunction "CS_DIS_1_6") (pintype "input"))
      (node (ref "IC1") (pin "8") (pinfunction "CS_DIS_2_8") (pintype "input"))
      (node (ref "R11") (pin "1") (pinfunction "1_1") (pintype "passive"))
      (node (ref "R12") (pin "2") (pinfunction "2_2") (pintype "passive"))
    )
    (net (code "60") (name "Net-(IC1-ENA{slash}DIAGA)") (class "Default")
      (node (ref "IC1") (pin "5") (pinfunction "ENA/DIAGA_5") (pintype "passive"))
      (node (ref "R3") (pin "1") (pinfunction "1_1") (pintype "passive"))
    )
    (net (code "61") (name "Net-(IC1-ENB{slash}DIAGB)") (class "Default")
      (node (ref "IC1") (pin "9") (pinfunction "ENB/DIAGB_9") (pintype "passive"))
      (node (ref "R2") (pin "1") (pinfunction "1_1") (pintype "passive"))
    )
    (net (code "62") (name "Net-(IC1-INA)") (class "Default")
      (node (ref "IC1") (pin "4") (pinfunction "INA_4") (pintype "input"))
      (node (ref "R7") (pin "1") (pinfunction "1_1") (pintype "passive"))
    )
    (net (code "63") (name "Net-(IC1-INB)") (class "Default")
      (node (ref "IC1") (pin "10") (pinfunction "INB_10") (pintype "input"))
      (node (ref "R10") (pin "1") (pinfunction "1_1") (pintype "passive"))
    )
    (net (code "64") (name "Net-(IC1-PWM)") (class "Default")
      (node (ref "IC1") (pin "7") (pinfunction "PWM_7") (pintype "passive"))
      (node (ref "R8") (pin "1") (pinfunction "1_1") (pintype "passive"))
    )
    (net (code "65") (name "Net-(IC2-CS_DIS_1)") (class "Default")
      (node (ref "IC2") (pin "6") (pinfunction "CS_DIS_1_6") (pintype "input"))
      (node (ref "IC2") (pin "8") (pinfunction "CS_DIS_2_8") (pintype "input"))
      (node (ref "R27") (pin "1") (pinfunction "1_1") (pintype "passive"))
      (node (ref "R28") (pin "2") (pinfunction "2_2") (pintype "passive"))
    )
    (net (code "66") (name "Net-(IC2-ENA{slash}DIAGA)") (class "Default")
      (node (ref "IC2") (pin "5") (pinfunction "ENA/DIAGA_5") (pintype "passive"))
      (node (ref "R18") (pin "1") (pinfunction "1_1") (pintype "passive"))
    )
    (net (code "67") (name "Net-(IC2-ENB{slash}DIAGB)") (class "Default")
      (node (ref "IC2") (pin "9") (pinfunction "ENB/DIAGB_9") (pintype "passive"))
      (node (ref "R17") (pin "1") (pinfunction "1_1") (pintype "passive"))
    )
    (net (code "68") (name "Net-(IC2-INA)") (class "Default")
      (node (ref "IC2") (pin "4") (pinfunction "INA_4") (pintype "input"))
      (node (ref "R22") (pin "1") (pinfunction "1_1") (pintype "passive"))
    )
    (net (code "69") (name "Net-(IC2-INB)") (class "Default")
      (node (ref "IC2") (pin "10") (pinfunction "INB_10") (pintype "input"))
      (node (ref "R25") (pin "1") (pinfunction "1_1") (pintype "passive"))
    )
    (net (code "70") (name "Net-(IC2-PWM)") (class "Default")
      (node (ref "IC2") (pin "7") (pinfunction "PWM_7") (pintype "passive"))
      (node (ref "R23") (pin "1") (pinfunction "1_1") (pintype "passive"))
    )
    (net (code "71") (name "Net-(K1-T1)") (class "Default")
      (node (ref "K1") (pin "4") (pinfunction "T1_4") (pintype "passive"))
      (node (ref "Q11") (pin "1") (pinfunction "D_1") (pintype "passive"))
    )
    (net (code "72") (name "Net-(Q10-G)") (class "Default")
      (node (ref "Q10") (pin "2") (pinfunction "G_2") (pintype "passive"))
      (node (ref "R30") (pin "1") (pinfunction "1_1") (pintype "passive"))
      (node (ref "R31") (pin "2") (pinfunction "2_2") (pintype "passive"))
    )
    (net (code "73") (name "Net-(U1A-BOOT0)") (class "Default")
      (node (ref "R33") (pin "2") (pinfunction "2_2") (pintype "passive"))
      (node (ref "U1") (pin "44") (pinfunction "BOOT0_44") (pintype "input"))
    )
    (net (code "74") (name "Net-(U1A-NRST)") (class "Default")
      (node (ref "C7") (pin "2") (pinfunction "2_2") (pintype "passive"))
      (node (ref "R32") (pin "1") (pinfunction "1_1") (pintype "passive"))
      (node (ref "S1") (pin "1") (pinfunction "1_1") (pintype "passive"))
      (node (ref "U1") (pin "7") (pinfunction "NRST_7") (pintype "bidirectional"))
    )
    (net (code "75") (name "Net-(U1A-PB0)") (class "Default")
      (node (ref "R19") (pin "1") (pinfunction "1_1") (pintype "passive"))
      (node (ref "U1") (pin "18") (pinfunction "PB0_18") (pintype "bidirectional"))
    )
    (net (code "76") (name "Net-(U1A-PB1)") (class "Default")
      (node (ref "R20") (pin "1") (pinfunction "1_1") (pintype "passive"))
      (node (ref "U1") (pin "19") (pinfunction "PB1_19") (pintype "bidirectional"))
    )
    (net (code "77") (name "Net-(U1A-PB2)") (class "Default")
      (node (ref "R21") (pin "1") (pinfunction "1_1") (pintype "passive"))
      (node (ref "U1") (pin "20") (pinfunction "PB2_20") (pintype "bidirectional"))
    )
    (net (code "78") (name "Net-(U1A-PD0-OSC_IN)") (class "Default")
      (node (ref "C5") (pin "2") (pinfunction "2_2") (pintype "passive"))
      (node (ref "U1") (pin "5") (pinfunction "PD0-OSC_IN_5") (pintype "bidirectional"))
      (node (ref "Y1") (pin "2") (pinfunction "OSC2_2") (pintype "passive"))
    )
    (net (code "79") (name "Net-(U1A-PD1-OSC_OUT)") (class "Default")
      (node (ref "C6") (pin "2") (pinfunction "2_2") (pintype "passive"))
      (node (ref "U1") (pin "6") (pinfunction "PD1-OSC_OUT_6") (pintype "bidirectional"))
      (node (ref "Y1") (pin "1") (pinfunction "OSC1_1") (pintype "passive"))
    )
    (net (code "80") (name "unconnected-(IC1-NC_1-Pad2)") (class "Default")
      (node (ref "IC1") (pin "2") (pinfunction "NC_1_2") (pintype "passive+no_connect"))
    )
    (net (code "81") (name "unconnected-(IC1-NC_2-Pad14)") (class "Default")
      (node (ref "IC1") (pin "14") (pinfunction "NC_2_14") (pintype "passive+no_connect"))
    )
    (net (code "82") (name "unconnected-(IC1-NC_3-Pad17)") (class "Default")
      (node (ref "IC1") (pin "17") (pinfunction "NC_3_17") (pintype "passive+no_connect"))
    )
    (net (code "83") (name "unconnected-(IC1-NC_4-Pad24)") (class "Default")
      (node (ref "IC1") (pin "24") (pinfunction "NC_4_24") (pintype "passive+no_connect"))
    )
    (net (code "84") (name "unconnected-(IC1-NC_5-Pad29)") (class "Default")
      (node (ref "IC1") (pin "29") (pinfunction "NC_5_29") (pintype "passive+no_connect"))
    )
    (net (code "85") (name "unconnected-(IC1-NV-Pad22)") (class "Default")
      (node (ref "IC1") (pin "22") (pinfunction "NV_22") (pintype "passive+no_connect"))
    )
    (net (code "86") (name "unconnected-(IC2-NC_1-Pad2)") (class "Default")
      (node (ref "IC2") (pin "2") (pinfunction "NC_1_2") (pintype "passive+no_connect"))
    )
    (net (code "87") (name "unconnected-(IC2-NC_2-Pad14)") (class "Default")
      (node (ref "IC2") (pin "14") (pinfunction "NC_2_14") (pintype "passive+no_connect"))
    )
    (net (code "88") (name "unconnected-(IC2-NC_3-Pad17)") (class "Default")
      (node (ref "IC2") (pin "17") (pinfunction "NC_3_17") (pintype "passive+no_connect"))
    )
    (net (code "89") (name "unconnected-(IC2-NC_4-Pad24)") (class "Default")
      (node (ref "IC2") (pin "24") (pinfunction "NC_4_24") (pintype "passive+no_connect"))
    )
    (net (code "90") (name "unconnected-(IC2-NC_5-Pad29)") (class "Default")
      (node (ref "IC2") (pin "29") (pinfunction "NC_5_29") (pintype "passive+no_connect"))
    )
    (net (code "91") (name "unconnected-(IC2-NV-Pad22)") (class "Default")
      (node (ref "IC2") (pin "22") (pinfunction "NV_22") (pintype "passive+no_connect"))
    )
    (net (code "92") (name "unconnected-(K1-COM-Pad1)") (class "Default")
      (node (ref "K1") (pin "1") (pinfunction "COM_1") (pintype "passive"))
    )
    (net (code "93") (name "unconnected-(Motor1-Pad3)") (class "Default")
      (node (ref "Motor1") (pin "3") (pinfunction "3_3") (pintype "passive"))
    )
    (net (code "94") (name "unconnected-(Motor1-Pad4)") (class "Default")
      (node (ref "Motor1") (pin "4") (pinfunction "4_4") (pintype "passive"))
    )
    (net (code "95") (name "unconnected-(Motor3-Pad3)") (class "Default")
      (node (ref "Motor3") (pin "3") (pinfunction "3_3") (pintype "passive"))
    )
    (net (code "96") (name "unconnected-(Motor3-Pad4)") (class "Default")
      (node (ref "Motor3") (pin "4") (pinfunction "4_4") (pintype "passive"))
    )
    (net (code "97") (name "unconnected-(U1A-PA12-Pad33)") (class "Default")
      (node (ref "U1") (pin "33") (pinfunction "PA12_33") (pintype "bidirectional"))
    )
    (net (code "98") (name "unconnected-(U1A-PA15-Pad38)") (class "Default")
      (node (ref "U1") (pin "38") (pinfunction "PA15_38") (pintype "bidirectional"))
    )
    (net (code "99") (name "unconnected-(U1A-PB3-Pad39)") (class "Default")
      (node (ref "U1") (pin "39") (pinfunction "PB3_39") (pintype "bidirectional"))
    )
    (net (code "100") (name "unconnected-(U2-NC-Pad4)") (class "Default")
      (node (ref "U2") (pin "4") (pinfunction "NC_4") (pintype "passive+no_connect"))
    )
  )
)
